# hw3.net
KiCad netlist of a schematic drawn in EAGLE
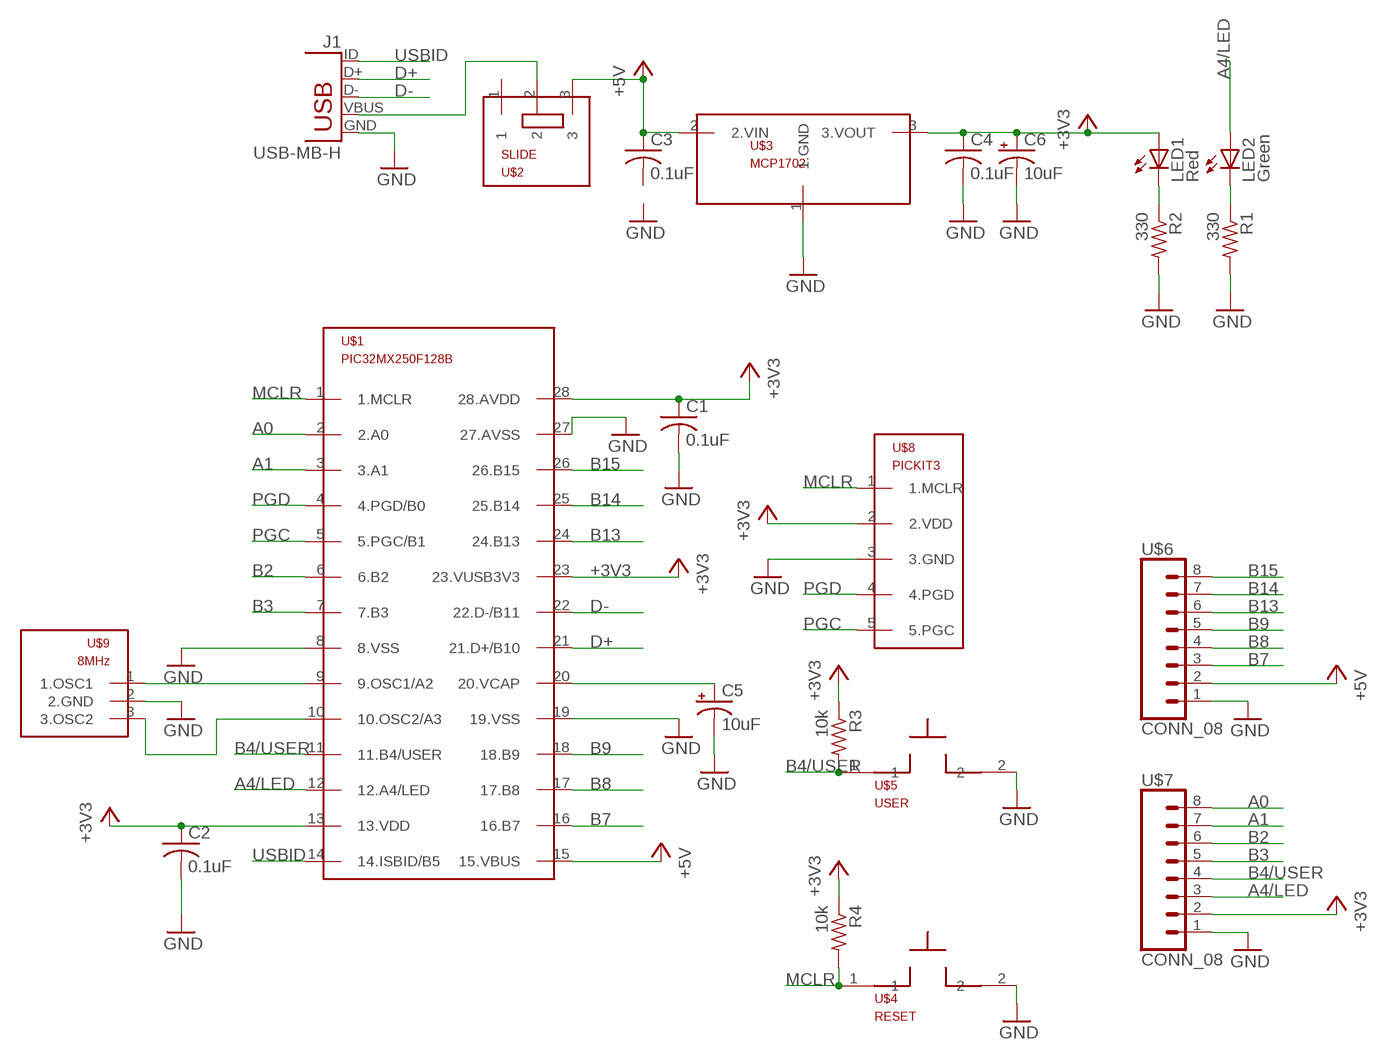
[diagram p0: schematic, sheet 1]

(export (version "E")
  (design (tool "Eeschema 10.0.6"))
  (components
    (comp (ref "C1")
      (value "0.1uF")
      (footprint "eagle-import:C025-025X050")
      (libsource (lib "eagle-import") (part "C-US025-025X050"))
    )
    (comp (ref "C2")
      (value "0.1uF")
      (footprint "eagle-import:C025-025X050")
      (libsource (lib "eagle-import") (part "C-US025-025X050"))
    )
    (comp (ref "C3")
      (value "0.1uF")
      (footprint "eagle-import:C025-025X050")
      (libsource (lib "eagle-import") (part "C-US025-025X050"))
    )
    (comp (ref "C4")
      (value "0.1uF")
      (footprint "eagle-import:C025-025X050")
      (libsource (lib "eagle-import") (part "C-US025-025X050"))
    )
    (comp (ref "C5")
      (value "10uF")
      (footprint "eagle-import:B45181B")
      (libsource (lib "eagle-import") (part "CPOL-USB45181B"))
    )
    (comp (ref "C6")
      (value "10uF")
      (footprint "eagle-import:B45181B")
      (libsource (lib "eagle-import") (part "CPOL-USB45181B"))
    )
    (comp (ref "J1")
      (value "USB-MB-H")
      (footprint "eagle-import:USB-MB-H")
      (libsource (lib "eagle-import") (part "USB-MB-H"))
    )
    (comp (ref "LED1")
      (value "Red")
      (footprint "eagle-import:LED3MM")
      (libsource (lib "eagle-import") (part "LED3MM"))
    )
    (comp (ref "LED2")
      (value "Green")
      (footprint "eagle-import:LED3MM")
      (libsource (lib "eagle-import") (part "LED3MM"))
    )
    (comp (ref "R1")
      (value "330")
      (footprint "eagle-import:0207_10")
      (libsource (lib "eagle-import") (part "R-US_0207/10"))
    )
    (comp (ref "R2")
      (value "330")
      (footprint "eagle-import:0207_10")
      (libsource (lib "eagle-import") (part "R-US_0207/10"))
    )
    (comp (ref "R3")
      (value "10k")
      (footprint "eagle-import:0207_10")
      (libsource (lib "eagle-import") (part "R-US_0207/10"))
    )
    (comp (ref "R4")
      (value "10k")
      (footprint "eagle-import:0207_10")
      (libsource (lib "eagle-import") (part "R-US_0207/10"))
    )
    (comp (ref "U$1")
      (value "PIC32MX250F128B")
      (footprint "eagle-import:DIL28-3")
      (libsource (lib "eagle-import") (part "PIC32MX250F128B"))
    )
    (comp (ref "U$2")
      (value "SLIDE")
      (footprint "eagle-import:SLIDE")
      (libsource (lib "eagle-import") (part "SLIDE"))
    )
    (comp (ref "U$3")
      (value "MCP1702")
      (footprint "eagle-import:TO92")
      (libsource (lib "eagle-import") (part "MCP1702"))
    )
    (comp (ref "U$4")
      (value "RESET")
      (footprint "eagle-import:PB")
      (libsource (lib "eagle-import") (part "PB"))
    )
    (comp (ref "U$5")
      (value "USER")
      (footprint "eagle-import:PB")
      (libsource (lib "eagle-import") (part "PB"))
    )
    (comp (ref "U$6")
      (value "CONN_08")
      (footprint "eagle-import:1X08")
      (libsource (lib "eagle-import") (part "CONN_08"))
    )
    (comp (ref "U$7")
      (value "CONN_08")
      (footprint "eagle-import:1X08")
      (libsource (lib "eagle-import") (part "CONN_08"))
    )
    (comp (ref "U$8")
      (value "PICKIT3")
      (footprint "eagle-import:1X05")
      (libsource (lib "eagle-import") (part "PICKIT3"))
    )
    (comp (ref "U$9")
      (value "8MHz")
      (footprint "eagle-import:OSC")
      (libsource (lib "eagle-import") (part "OSCOSC"))
    )
  )
  (nets
    (net (code "1") (name "+3V3") (class "Default")
      (node (ref "C1") (pin "1") (pinfunction "1_1") (pintype "passive"))
      (node (ref "C2") (pin "1") (pinfunction "1_1") (pintype "passive"))
      (node (ref "C4") (pin "1") (pinfunction "1_1") (pintype "passive"))
      (node (ref "C6") (pin "+") (pinfunction "+_+") (pintype "passive"))
      (node (ref "LED1") (pin "A") (pinfunction "A_A") (pintype "passive"))
      (node (ref "R3") (pin "1") (pinfunction "1_1") (pintype "passive"))
      (node (ref "R4") (pin "1") (pinfunction "1_1") (pintype "passive"))
      (node (ref "U$1") (pin "13") (pinfunction "13.VDD_13") (pintype "bidirectional"))
      (node (ref "U$1") (pin "23") (pinfunction "23.VUSB3V3_23") (pintype "bidirectional"))
      (node (ref "U$1") (pin "28") (pinfunction "28.AVDD_28") (pintype "bidirectional"))
      (node (ref "U$3") (pin "3") (pinfunction "3.VOUT_3") (pintype "bidirectional"))
      (node (ref "U$7") (pin "2") (pinfunction "2_2") (pintype "passive"))
      (node (ref "U$8") (pin "2") (pinfunction "2.VDD_2") (pintype "bidirectional"))
    )
    (net (code "2") (name "+5V") (class "Default")
      (node (ref "C3") (pin "1") (pinfunction "1_1") (pintype "passive"))
      (node (ref "U$1") (pin "15") (pinfunction "15.VBUS_15") (pintype "bidirectional"))
      (node (ref "U$2") (pin "3") (pinfunction "3_3") (pintype "bidirectional"))
      (node (ref "U$3") (pin "2") (pinfunction "2.VIN_2") (pintype "bidirectional"))
      (node (ref "U$6") (pin "2") (pinfunction "2_2") (pintype "passive"))
    )
    (net (code "3") (name "/A0") (class "Default")
      (node (ref "U$1") (pin "2") (pinfunction "2.A0_2") (pintype "bidirectional"))
      (node (ref "U$7") (pin "8") (pinfunction "8_8") (pintype "passive"))
    )
    (net (code "4") (name "/A1") (class "Default")
      (node (ref "U$1") (pin "3") (pinfunction "3.A1_3") (pintype "bidirectional"))
      (node (ref "U$7") (pin "7") (pinfunction "7_7") (pintype "passive"))
    )
    (net (code "5") (name "/A4{slash}LED") (class "Default")
      (node (ref "LED2") (pin "A") (pinfunction "A_A") (pintype "passive"))
      (node (ref "U$1") (pin "12") (pinfunction "12.A4/LED_12") (pintype "bidirectional"))
      (node (ref "U$7") (pin "3") (pinfunction "3_3") (pintype "passive"))
    )
    (net (code "6") (name "/B2") (class "Default")
      (node (ref "U$1") (pin "6") (pinfunction "6.B2_6") (pintype "bidirectional"))
      (node (ref "U$7") (pin "6") (pinfunction "6_6") (pintype "passive"))
    )
    (net (code "7") (name "/B3") (class "Default")
      (node (ref "U$1") (pin "7") (pinfunction "7.B3_7") (pintype "bidirectional"))
      (node (ref "U$7") (pin "5") (pinfunction "5_5") (pintype "passive"))
    )
    (net (code "8") (name "/B4{slash}USER") (class "Default")
      (node (ref "R3") (pin "2") (pinfunction "2_2") (pintype "passive"))
      (node (ref "U$1") (pin "11") (pinfunction "11.B4/USER_11") (pintype "bidirectional"))
      (node (ref "U$5") (pin "1") (pinfunction "1_1") (pintype "bidirectional"))
      (node (ref "U$7") (pin "4") (pinfunction "4_4") (pintype "passive"))
    )
    (net (code "9") (name "/B7") (class "Default")
      (node (ref "U$1") (pin "16") (pinfunction "16.B7_16") (pintype "bidirectional"))
      (node (ref "U$6") (pin "3") (pinfunction "3_3") (pintype "passive"))
    )
    (net (code "10") (name "/B8") (class "Default")
      (node (ref "U$1") (pin "17") (pinfunction "17.B8_17") (pintype "bidirectional"))
      (node (ref "U$6") (pin "4") (pinfunction "4_4") (pintype "passive"))
    )
    (net (code "11") (name "/B9") (class "Default")
      (node (ref "U$1") (pin "18") (pinfunction "18.B9_18") (pintype "bidirectional"))
      (node (ref "U$6") (pin "5") (pinfunction "5_5") (pintype "passive"))
    )
    (net (code "12") (name "/B13") (class "Default")
      (node (ref "U$1") (pin "24") (pinfunction "24.B13_24") (pintype "bidirectional"))
      (node (ref "U$6") (pin "6") (pinfunction "6_6") (pintype "passive"))
    )
    (net (code "13") (name "/B14") (class "Default")
      (node (ref "U$1") (pin "25") (pinfunction "25.B14_25") (pintype "bidirectional"))
      (node (ref "U$6") (pin "7") (pinfunction "7_7") (pintype "passive"))
    )
    (net (code "14") (name "/B15") (class "Default")
      (node (ref "U$1") (pin "26") (pinfunction "26.B15_26") (pintype "bidirectional"))
      (node (ref "U$6") (pin "8") (pinfunction "8_8") (pintype "passive"))
    )
    (net (code "15") (name "/D+") (class "Default")
      (node (ref "J1") (pin "D+") (pinfunction "D+_D+") (pintype "bidirectional"))
      (node (ref "U$1") (pin "21") (pinfunction "21.D+/B10_21") (pintype "bidirectional"))
    )
    (net (code "16") (name "/D-") (class "Default")
      (node (ref "J1") (pin "D-") (pinfunction "D-_D-") (pintype "bidirectional"))
      (node (ref "U$1") (pin "22") (pinfunction "22.D-/B11_22") (pintype "bidirectional"))
    )
    (net (code "17") (name "/MCLR") (class "Default")
      (node (ref "R4") (pin "2") (pinfunction "2_2") (pintype "passive"))
      (node (ref "U$1") (pin "1") (pinfunction "1.MCLR_1") (pintype "bidirectional"))
      (node (ref "U$4") (pin "1") (pinfunction "1_1") (pintype "bidirectional"))
      (node (ref "U$8") (pin "1") (pinfunction "1.MCLR_1") (pintype "bidirectional"))
    )
    (net (code "18") (name "/PGC") (class "Default")
      (node (ref "U$1") (pin "5") (pinfunction "5.PGC/B1_5") (pintype "bidirectional"))
      (node (ref "U$8") (pin "5") (pinfunction "5.PGC_5") (pintype "bidirectional"))
    )
    (net (code "19") (name "/PGD") (class "Default")
      (node (ref "U$1") (pin "4") (pinfunction "4.PGD/B0_4") (pintype "bidirectional"))
      (node (ref "U$8") (pin "4") (pinfunction "4.PGD_4") (pintype "bidirectional"))
    )
    (net (code "20") (name "/USBID") (class "Default")
      (node (ref "J1") (pin "ID") (pinfunction "ID_ID") (pintype "bidirectional"))
      (node (ref "U$1") (pin "14") (pinfunction "14.ISBID/B5_14") (pintype "bidirectional"))
    )
    (net (code "21") (name "GND") (class "Default")
      (node (ref "C1") (pin "2") (pinfunction "2_2") (pintype "passive"))
      (node (ref "C2") (pin "2") (pinfunction "2_2") (pintype "passive"))
      (node (ref "C4") (pin "2") (pinfunction "2_2") (pintype "passive"))
      (node (ref "C5") (pin "-") (pinfunction "-_-") (pintype "passive"))
      (node (ref "C6") (pin "-") (pinfunction "-_-") (pintype "passive"))
      (node (ref "J1") (pin "GND") (pinfunction "GND_GND") (pintype "bidirectional"))
      (node (ref "R1") (pin "2") (pinfunction "2_2") (pintype "passive"))
      (node (ref "R2") (pin "2") (pinfunction "2_2") (pintype "passive"))
      (node (ref "U$1") (pin "19") (pinfunction "19.VSS_19") (pintype "bidirectional"))
      (node (ref "U$1") (pin "27") (pinfunction "27.AVSS_27") (pintype "bidirectional"))
      (node (ref "U$1") (pin "8") (pinfunction "8.VSS_8") (pintype "bidirectional"))
      (node (ref "U$3") (pin "1") (pinfunction "1.GND_1") (pintype "bidirectional"))
      (node (ref "U$4") (pin "2") (pinfunction "2_2") (pintype "bidirectional"))
      (node (ref "U$5") (pin "2") (pinfunction "2_2") (pintype "bidirectional"))
      (node (ref "U$6") (pin "1") (pinfunction "1_1") (pintype "passive"))
      (node (ref "U$7") (pin "1") (pinfunction "1_1") (pintype "passive"))
      (node (ref "U$8") (pin "3") (pinfunction "3.GND_3") (pintype "bidirectional"))
      (node (ref "U$9") (pin "2") (pinfunction "2.GND_2") (pintype "bidirectional"))
    )
    (net (code "22") (name "Net-(J1-PadVBUS)") (class "Default")
      (node (ref "J1") (pin "VBUS") (pinfunction "VBUS_VBUS") (pintype "bidirectional"))
      (node (ref "U$2") (pin "2") (pinfunction "2_2") (pintype "bidirectional"))
    )
    (net (code "23") (name "Net-(LED1-C)") (class "Default")
      (node (ref "LED1") (pin "K") (pinfunction "C_K") (pintype "passive"))
      (node (ref "R2") (pin "1") (pinfunction "1_1") (pintype "passive"))
    )
    (net (code "24") (name "Net-(LED2-C)") (class "Default")
      (node (ref "LED2") (pin "K") (pinfunction "C_K") (pintype "passive"))
      (node (ref "R1") (pin "1") (pinfunction "1_1") (pintype "passive"))
    )
    (net (code "25") (name "Net-(U$1-9.OSC1{slash}A2)") (class "Default")
      (node (ref "U$1") (pin "9") (pinfunction "9.OSC1/A2_9") (pintype "bidirectional"))
      (node (ref "U$9") (pin "1") (pinfunction "1.OSC1_1") (pintype "bidirectional"))
    )
    (net (code "26") (name "Net-(U$1-10.OSC2{slash}A3)") (class "Default")
      (node (ref "U$1") (pin "10") (pinfunction "10.OSC2/A3_10") (pintype "bidirectional"))
      (node (ref "U$9") (pin "3") (pinfunction "3.OSC2_3") (pintype "bidirectional"))
    )
    (net (code "27") (name "Net-(U$1-20.VCAP)") (class "Default")
      (node (ref "C5") (pin "+") (pinfunction "+_+") (pintype "passive"))
      (node (ref "U$1") (pin "20") (pinfunction "20.VCAP_20") (pintype "bidirectional"))
    )
    (net (code "28") (name "unconnected-(C3-Pad2)") (class "Default")
      (node (ref "C3") (pin "2") (pinfunction "2_2") (pintype "passive"))
    )
    (net (code "29") (name "unconnected-(U$2-Pad1)") (class "Default")
      (node (ref "U$2") (pin "1") (pinfunction "1_1") (pintype "bidirectional"))
    )
  )
)
